# digitalclock.net
KiCad netlist of a schematic drawn in EAGLE
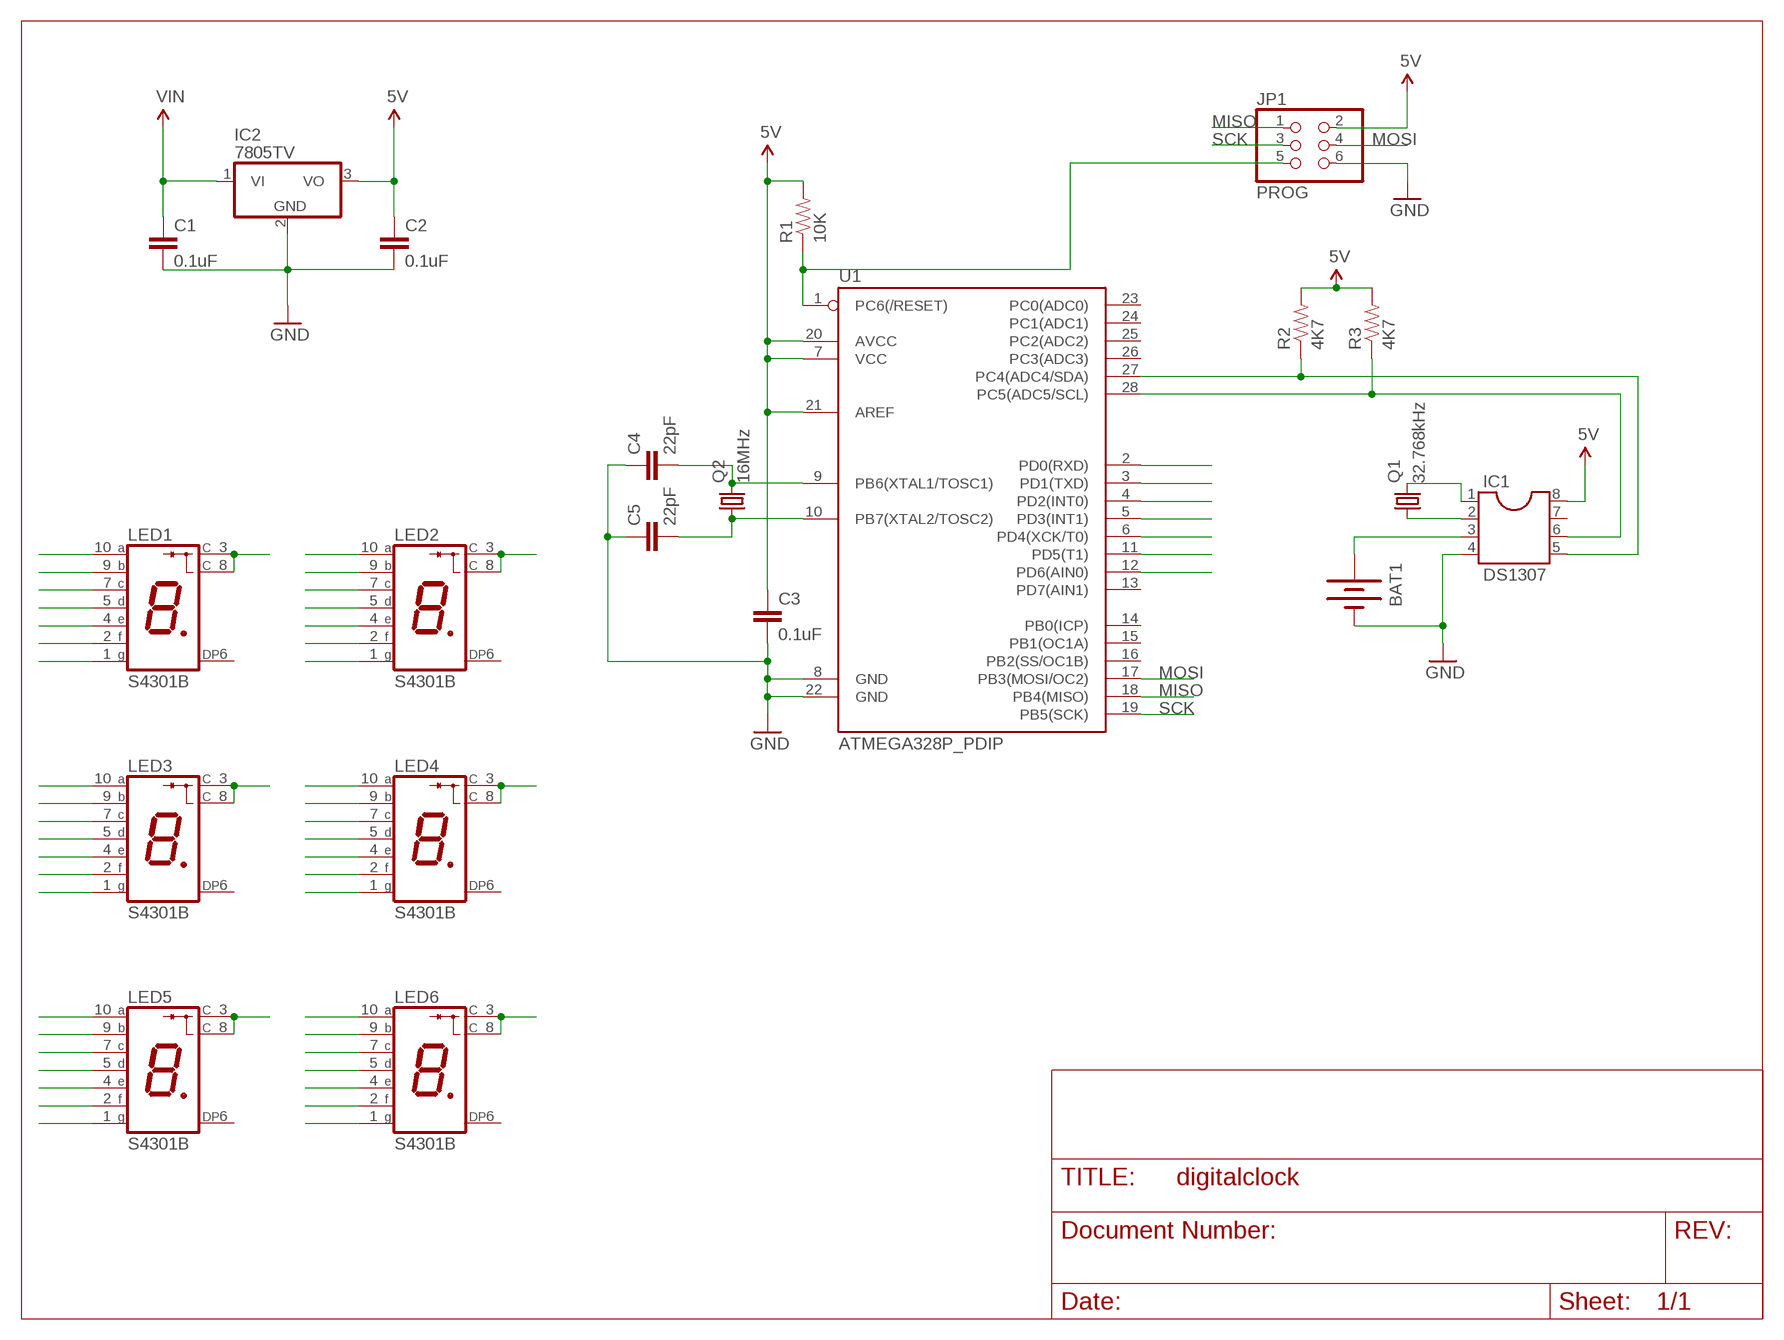
[diagram p0: schematic, sheet 1]

(export (version "E")
  (design (tool "Eeschema 10.0.6"))
  (components
    (comp (ref "BAT1")
      (value "BATTERY20PTH")
      (footprint "eagle-import:BATTCOM_20MM_PTH")
      (libsource (lib "eagle-import") (part "BATTERY20PTH"))
    )
    (comp (ref "C1")
      (value "0.1uF")
      (footprint "eagle-import:CAP-PTH-SMALL")
      (libsource (lib "eagle-import") (part "CAPPTH"))
    )
    (comp (ref "C2")
      (value "0.1uF")
      (footprint "eagle-import:CAP-PTH-SMALL")
      (libsource (lib "eagle-import") (part "CAPPTH"))
    )
    (comp (ref "C3")
      (value "0.1uF")
      (footprint "eagle-import:CAP-PTH-SMALL")
      (libsource (lib "eagle-import") (part "CAPPTH"))
    )
    (comp (ref "C4")
      (value "22pF")
      (footprint "eagle-import:CAP-PTH-SMALL")
      (libsource (lib "eagle-import") (part "CAPPTH"))
    )
    (comp (ref "C5")
      (value "22pF")
      (footprint "eagle-import:CAP-PTH-SMALL")
      (libsource (lib "eagle-import") (part "CAPPTH"))
    )
    (comp (ref "IC1")
      (value "DS1307")
      (footprint "eagle-import:SOCKET-08")
      (libsource (lib "eagle-import") (part "DIL8S"))
    )
    (comp (ref "IC2")
      (value "7805TV")
      (footprint "eagle-import:TO220V")
      (libsource (lib "eagle-import") (part "78TV05"))
    )
    (comp (ref "JP1")
      (value "PROG")
      (footprint "eagle-import:2X03")
      (libsource (lib "eagle-import") (part "PINHD-2X3"))
    )
    (comp (ref "LED1")
      (value "S4301B")
      (footprint "eagle-import:S4301B")
      (libsource (lib "eagle-import") (part "S4301B"))
    )
    (comp (ref "LED2")
      (value "S4301B")
      (footprint "eagle-import:S4301B")
      (libsource (lib "eagle-import") (part "S4301B"))
    )
    (comp (ref "LED3")
      (value "S4301B")
      (footprint "eagle-import:S4301B")
      (libsource (lib "eagle-import") (part "S4301B"))
    )
    (comp (ref "LED4")
      (value "S4301B")
      (footprint "eagle-import:S4301B")
      (libsource (lib "eagle-import") (part "S4301B"))
    )
    (comp (ref "LED5")
      (value "S4301B")
      (footprint "eagle-import:S4301B")
      (libsource (lib "eagle-import") (part "S4301B"))
    )
    (comp (ref "LED6")
      (value "S4301B")
      (footprint "eagle-import:S4301B")
      (libsource (lib "eagle-import") (part "S4301B"))
    )
    (comp (ref "Q1")
      (value "32.768kHz")
      (footprint "eagle-import:TC26V")
      (libsource (lib "eagle-import") (part "CRYSTALTC26V"))
    )
    (comp (ref "Q2")
      (value "16MHz")
      (footprint "eagle-import:HC49_S")
      (libsource (lib "eagle-import") (part "CRYSTALHC49S"))
    )
    (comp (ref "R1")
      (value "10K")
      (footprint "eagle-import:AXIAL-0.3")
      (libsource (lib "eagle-import") (part "RESISTORAXIAL-0.3"))
    )
    (comp (ref "R2")
      (value "4K7")
      (footprint "eagle-import:AXIAL-0.3")
      (libsource (lib "eagle-import") (part "RESISTORAXIAL-0.3"))
    )
    (comp (ref "R3")
      (value "4K7")
      (footprint "eagle-import:AXIAL-0.3")
      (libsource (lib "eagle-import") (part "RESISTORAXIAL-0.3"))
    )
    (comp (ref "U1")
      (value "ATMEGA328P_PDIP")
      (footprint "eagle-import:DIL28-3")
      (libsource (lib "eagle-import") (part "ATMEGA328P_PDIP"))
    )
  )
  (nets
    (net (code "1") (name "/MISO") (class "Default")
      (node (ref "JP1") (pin "1") (pinfunction "1_1") (pintype "passive"))
      (node (ref "U1") (pin "18") (pinfunction "PB4(MISO)_18") (pintype "bidirectional"))
    )
    (net (code "2") (name "/MOSI") (class "Default")
      (node (ref "JP1") (pin "4") (pinfunction "4_4") (pintype "passive"))
      (node (ref "U1") (pin "17") (pinfunction "PB3(MOSI/OC2)_17") (pintype "bidirectional"))
    )
    (net (code "3") (name "/SCK") (class "Default")
      (node (ref "JP1") (pin "3") (pinfunction "3_3") (pintype "passive"))
      (node (ref "U1") (pin "19") (pinfunction "PB5(SCK)_19") (pintype "bidirectional"))
    )
    (net (code "4") (name "5V") (class "Default")
      (node (ref "C2") (pin "1") (pinfunction "1_1") (pintype "passive"))
      (node (ref "C3") (pin "1") (pinfunction "1_1") (pintype "passive"))
      (node (ref "IC1") (pin "8") (pinfunction "8_8") (pintype "passive"))
      (node (ref "IC2") (pin "3") (pinfunction "VO_3") (pintype "passive"))
      (node (ref "JP1") (pin "2") (pinfunction "2_2") (pintype "passive"))
      (node (ref "R1") (pin "P$2") (pinfunction "2_P$2") (pintype "passive"))
      (node (ref "R2") (pin "P$2") (pinfunction "2_P$2") (pintype "passive"))
      (node (ref "R3") (pin "P$2") (pinfunction "2_P$2") (pintype "passive"))
      (node (ref "U1") (pin "20") (pinfunction "AVCC_20") (pintype "bidirectional"))
      (node (ref "U1") (pin "21") (pinfunction "AREF_21") (pintype "bidirectional"))
      (node (ref "U1") (pin "7") (pinfunction "VCC_7") (pintype "bidirectional"))
    )
    (net (code "5") (name "GND") (class "Default")
      (node (ref "BAT1") (pin "2") (pinfunction "-_2") (pintype "power_in"))
      (node (ref "C1") (pin "2") (pinfunction "2_2") (pintype "passive"))
      (node (ref "C2") (pin "2") (pinfunction "2_2") (pintype "passive"))
      (node (ref "C3") (pin "2") (pinfunction "2_2") (pintype "passive"))
      (node (ref "C4") (pin "1") (pinfunction "1_1") (pintype "passive"))
      (node (ref "C5") (pin "1") (pinfunction "1_1") (pintype "passive"))
      (node (ref "IC1") (pin "4") (pinfunction "4_4") (pintype "passive"))
      (node (ref "IC2") (pin "2") (pinfunction "GND_2") (pintype "passive"))
      (node (ref "JP1") (pin "6") (pinfunction "6_6") (pintype "passive"))
      (node (ref "U1") (pin "22") (pinfunction "GND_22") (pintype "bidirectional"))
      (node (ref "U1") (pin "8") (pinfunction "GND_8") (pintype "bidirectional"))
    )
    (net (code "6") (name "Net-(BAT1-+)") (class "Default")
      (node (ref "BAT1") (pin "1") (pinfunction "+_1") (pintype "power_in"))
      (node (ref "IC1") (pin "3") (pinfunction "3_3") (pintype "passive"))
    )
    (net (code "7") (name "Net-(IC1-Pad1)") (class "Default")
      (node (ref "IC1") (pin "1") (pinfunction "1_1") (pintype "passive"))
      (node (ref "Q1") (pin "2") (pinfunction "2_2") (pintype "passive"))
    )
    (net (code "8") (name "Net-(IC1-Pad2)") (class "Default")
      (node (ref "IC1") (pin "2") (pinfunction "2_2") (pintype "passive"))
      (node (ref "Q1") (pin "1") (pinfunction "1_1") (pintype "passive"))
    )
    (net (code "9") (name "Net-(LED1-C-Pad3)") (class "Default")
      (node (ref "LED1") (pin "3") (pinfunction "C_3") (pintype "passive"))
      (node (ref "LED1") (pin "8") (pinfunction "C_8") (pintype "passive"))
    )
    (net (code "10") (name "Net-(LED2-C-Pad3)") (class "Default")
      (node (ref "LED2") (pin "3") (pinfunction "C_3") (pintype "passive"))
      (node (ref "LED2") (pin "8") (pinfunction "C_8") (pintype "passive"))
    )
    (net (code "11") (name "Net-(LED3-C-Pad3)") (class "Default")
      (node (ref "LED3") (pin "3") (pinfunction "C_3") (pintype "passive"))
      (node (ref "LED3") (pin "8") (pinfunction "C_8") (pintype "passive"))
    )
    (net (code "12") (name "Net-(LED4-C-Pad3)") (class "Default")
      (node (ref "LED4") (pin "3") (pinfunction "C_3") (pintype "passive"))
      (node (ref "LED4") (pin "8") (pinfunction "C_8") (pintype "passive"))
    )
    (net (code "13") (name "Net-(LED5-C-Pad3)") (class "Default")
      (node (ref "LED5") (pin "3") (pinfunction "C_3") (pintype "passive"))
      (node (ref "LED5") (pin "8") (pinfunction "C_8") (pintype "passive"))
    )
    (net (code "14") (name "Net-(LED6-C-Pad3)") (class "Default")
      (node (ref "LED6") (pin "3") (pinfunction "C_3") (pintype "passive"))
      (node (ref "LED6") (pin "8") (pinfunction "C_8") (pintype "passive"))
    )
    (net (code "15") (name "Net-(R1-1)") (class "Default")
      (node (ref "JP1") (pin "5") (pinfunction "5_5") (pintype "passive"))
      (node (ref "R1") (pin "P$1") (pinfunction "1_P$1") (pintype "passive"))
      (node (ref "U1") (pin "1") (pinfunction "PC6(/RESET)_1") (pintype "bidirectional"))
    )
    (net (code "16") (name "Net-(R2-1)") (class "Default")
      (node (ref "IC1") (pin "5") (pinfunction "5_5") (pintype "passive"))
      (node (ref "R2") (pin "P$1") (pinfunction "1_P$1") (pintype "passive"))
      (node (ref "U1") (pin "27") (pinfunction "PC4(ADC4/SDA)_27") (pintype "bidirectional"))
    )
    (net (code "17") (name "Net-(R3-1)") (class "Default")
      (node (ref "IC1") (pin "6") (pinfunction "6_6") (pintype "passive"))
      (node (ref "R3") (pin "P$1") (pinfunction "1_P$1") (pintype "passive"))
      (node (ref "U1") (pin "28") (pinfunction "PC5(ADC5/SCL)_28") (pintype "bidirectional"))
    )
    (net (code "18") (name "Net-(U1-PB6(XTAL1{slash}TOSC1))") (class "Default")
      (node (ref "C4") (pin "2") (pinfunction "2_2") (pintype "passive"))
      (node (ref "Q2") (pin "2") (pinfunction "2_2") (pintype "passive"))
      (node (ref "U1") (pin "9") (pinfunction "PB6(XTAL1/TOSC1)_9") (pintype "bidirectional"))
    )
    (net (code "19") (name "Net-(U1-PB7(XTAL2{slash}TOSC2))") (class "Default")
      (node (ref "C5") (pin "2") (pinfunction "2_2") (pintype "passive"))
      (node (ref "Q2") (pin "1") (pinfunction "1_1") (pintype "passive"))
      (node (ref "U1") (pin "10") (pinfunction "PB7(XTAL2/TOSC2)_10") (pintype "bidirectional"))
    )
    (net (code "20") (name "VIN") (class "Default")
      (node (ref "C1") (pin "1") (pinfunction "1_1") (pintype "passive"))
      (node (ref "IC2") (pin "1") (pinfunction "VI_1") (pintype "input"))
    )
    (net (code "21") (name "unconnected-(IC1-Pad7)") (class "Default")
      (node (ref "IC1") (pin "7") (pinfunction "7_7") (pintype "passive"))
    )
    (net (code "22") (name "unconnected-(LED1-A-Pad10)") (class "Default")
      (node (ref "LED1") (pin "10") (pinfunction "A_10") (pintype "passive"))
    )
    (net (code "23") (name "unconnected-(LED1-B-Pad9)") (class "Default")
      (node (ref "LED1") (pin "9") (pinfunction "B_9") (pintype "passive"))
    )
    (net (code "24") (name "unconnected-(LED1-C-Pad7)") (class "Default")
      (node (ref "LED1") (pin "7") (pinfunction "C_7") (pintype "passive"))
    )
    (net (code "25") (name "unconnected-(LED1-D-Pad5)") (class "Default")
      (node (ref "LED1") (pin "5") (pinfunction "D_5") (pintype "passive"))
    )
    (net (code "26") (name "unconnected-(LED1-DP-Pad6)") (class "Default")
      (node (ref "LED1") (pin "6") (pinfunction "DP_6") (pintype "passive"))
    )
    (net (code "27") (name "unconnected-(LED1-E-Pad4)") (class "Default")
      (node (ref "LED1") (pin "4") (pinfunction "E_4") (pintype "passive"))
    )
    (net (code "28") (name "unconnected-(LED1-F-Pad2)") (class "Default")
      (node (ref "LED1") (pin "2") (pinfunction "F_2") (pintype "passive"))
    )
    (net (code "29") (name "unconnected-(LED1-G-Pad1)") (class "Default")
      (node (ref "LED1") (pin "1") (pinfunction "G_1") (pintype "passive"))
    )
    (net (code "30") (name "unconnected-(LED2-A-Pad10)") (class "Default")
      (node (ref "LED2") (pin "10") (pinfunction "A_10") (pintype "passive"))
    )
    (net (code "31") (name "unconnected-(LED2-B-Pad9)") (class "Default")
      (node (ref "LED2") (pin "9") (pinfunction "B_9") (pintype "passive"))
    )
    (net (code "32") (name "unconnected-(LED2-C-Pad7)") (class "Default")
      (node (ref "LED2") (pin "7") (pinfunction "C_7") (pintype "passive"))
    )
    (net (code "33") (name "unconnected-(LED2-D-Pad5)") (class "Default")
      (node (ref "LED2") (pin "5") (pinfunction "D_5") (pintype "passive"))
    )
    (net (code "34") (name "unconnected-(LED2-DP-Pad6)") (class "Default")
      (node (ref "LED2") (pin "6") (pinfunction "DP_6") (pintype "passive"))
    )
    (net (code "35") (name "unconnected-(LED2-E-Pad4)") (class "Default")
      (node (ref "LED2") (pin "4") (pinfunction "E_4") (pintype "passive"))
    )
    (net (code "36") (name "unconnected-(LED2-F-Pad2)") (class "Default")
      (node (ref "LED2") (pin "2") (pinfunction "F_2") (pintype "passive"))
    )
    (net (code "37") (name "unconnected-(LED2-G-Pad1)") (class "Default")
      (node (ref "LED2") (pin "1") (pinfunction "G_1") (pintype "passive"))
    )
    (net (code "38") (name "unconnected-(LED3-A-Pad10)") (class "Default")
      (node (ref "LED3") (pin "10") (pinfunction "A_10") (pintype "passive"))
    )
    (net (code "39") (name "unconnected-(LED3-B-Pad9)") (class "Default")
      (node (ref "LED3") (pin "9") (pinfunction "B_9") (pintype "passive"))
    )
    (net (code "40") (name "unconnected-(LED3-C-Pad7)") (class "Default")
      (node (ref "LED3") (pin "7") (pinfunction "C_7") (pintype "passive"))
    )
    (net (code "41") (name "unconnected-(LED3-D-Pad5)") (class "Default")
      (node (ref "LED3") (pin "5") (pinfunction "D_5") (pintype "passive"))
    )
    (net (code "42") (name "unconnected-(LED3-DP-Pad6)") (class "Default")
      (node (ref "LED3") (pin "6") (pinfunction "DP_6") (pintype "passive"))
    )
    (net (code "43") (name "unconnected-(LED3-E-Pad4)") (class "Default")
      (node (ref "LED3") (pin "4") (pinfunction "E_4") (pintype "passive"))
    )
    (net (code "44") (name "unconnected-(LED3-F-Pad2)") (class "Default")
      (node (ref "LED3") (pin "2") (pinfunction "F_2") (pintype "passive"))
    )
    (net (code "45") (name "unconnected-(LED3-G-Pad1)") (class "Default")
      (node (ref "LED3") (pin "1") (pinfunction "G_1") (pintype "passive"))
    )
    (net (code "46") (name "unconnected-(LED4-A-Pad10)") (class "Default")
      (node (ref "LED4") (pin "10") (pinfunction "A_10") (pintype "passive"))
    )
    (net (code "47") (name "unconnected-(LED4-B-Pad9)") (class "Default")
      (node (ref "LED4") (pin "9") (pinfunction "B_9") (pintype "passive"))
    )
    (net (code "48") (name "unconnected-(LED4-C-Pad7)") (class "Default")
      (node (ref "LED4") (pin "7") (pinfunction "C_7") (pintype "passive"))
    )
    (net (code "49") (name "unconnected-(LED4-D-Pad5)") (class "Default")
      (node (ref "LED4") (pin "5") (pinfunction "D_5") (pintype "passive"))
    )
    (net (code "50") (name "unconnected-(LED4-DP-Pad6)") (class "Default")
      (node (ref "LED4") (pin "6") (pinfunction "DP_6") (pintype "passive"))
    )
    (net (code "51") (name "unconnected-(LED4-E-Pad4)") (class "Default")
      (node (ref "LED4") (pin "4") (pinfunction "E_4") (pintype "passive"))
    )
    (net (code "52") (name "unconnected-(LED4-F-Pad2)") (class "Default")
      (node (ref "LED4") (pin "2") (pinfunction "F_2") (pintype "passive"))
    )
    (net (code "53") (name "unconnected-(LED4-G-Pad1)") (class "Default")
      (node (ref "LED4") (pin "1") (pinfunction "G_1") (pintype "passive"))
    )
    (net (code "54") (name "unconnected-(LED5-A-Pad10)") (class "Default")
      (node (ref "LED5") (pin "10") (pinfunction "A_10") (pintype "passive"))
    )
    (net (code "55") (name "unconnected-(LED5-B-Pad9)") (class "Default")
      (node (ref "LED5") (pin "9") (pinfunction "B_9") (pintype "passive"))
    )
    (net (code "56") (name "unconnected-(LED5-C-Pad7)") (class "Default")
      (node (ref "LED5") (pin "7") (pinfunction "C_7") (pintype "passive"))
    )
    (net (code "57") (name "unconnected-(LED5-D-Pad5)") (class "Default")
      (node (ref "LED5") (pin "5") (pinfunction "D_5") (pintype "passive"))
    )
    (net (code "58") (name "unconnected-(LED5-DP-Pad6)") (class "Default")
      (node (ref "LED5") (pin "6") (pinfunction "DP_6") (pintype "passive"))
    )
    (net (code "59") (name "unconnected-(LED5-E-Pad4)") (class "Default")
      (node (ref "LED5") (pin "4") (pinfunction "E_4") (pintype "passive"))
    )
    (net (code "60") (name "unconnected-(LED5-F-Pad2)") (class "Default")
      (node (ref "LED5") (pin "2") (pinfunction "F_2") (pintype "passive"))
    )
    (net (code "61") (name "unconnected-(LED5-G-Pad1)") (class "Default")
      (node (ref "LED5") (pin "1") (pinfunction "G_1") (pintype "passive"))
    )
    (net (code "62") (name "unconnected-(LED6-A-Pad10)") (class "Default")
      (node (ref "LED6") (pin "10") (pinfunction "A_10") (pintype "passive"))
    )
    (net (code "63") (name "unconnected-(LED6-B-Pad9)") (class "Default")
      (node (ref "LED6") (pin "9") (pinfunction "B_9") (pintype "passive"))
    )
    (net (code "64") (name "unconnected-(LED6-C-Pad7)") (class "Default")
      (node (ref "LED6") (pin "7") (pinfunction "C_7") (pintype "passive"))
    )
    (net (code "65") (name "unconnected-(LED6-D-Pad5)") (class "Default")
      (node (ref "LED6") (pin "5") (pinfunction "D_5") (pintype "passive"))
    )
    (net (code "66") (name "unconnected-(LED6-DP-Pad6)") (class "Default")
      (node (ref "LED6") (pin "6") (pinfunction "DP_6") (pintype "passive"))
    )
    (net (code "67") (name "unconnected-(LED6-E-Pad4)") (class "Default")
      (node (ref "LED6") (pin "4") (pinfunction "E_4") (pintype "passive"))
    )
    (net (code "68") (name "unconnected-(LED6-F-Pad2)") (class "Default")
      (node (ref "LED6") (pin "2") (pinfunction "F_2") (pintype "passive"))
    )
    (net (code "69") (name "unconnected-(LED6-G-Pad1)") (class "Default")
      (node (ref "LED6") (pin "1") (pinfunction "G_1") (pintype "passive"))
    )
    (net (code "70") (name "unconnected-(U1-PB0(ICP)-Pad14)") (class "Default")
      (node (ref "U1") (pin "14") (pinfunction "PB0(ICP)_14") (pintype "bidirectional"))
    )
    (net (code "71") (name "unconnected-(U1-PB1(OC1A)-Pad15)") (class "Default")
      (node (ref "U1") (pin "15") (pinfunction "PB1(OC1A)_15") (pintype "bidirectional"))
    )
    (net (code "72") (name "unconnected-(U1-PB2(SS{slash}OC1B)-Pad16)") (class "Default")
      (node (ref "U1") (pin "16") (pinfunction "PB2(SS/OC1B)_16") (pintype "bidirectional"))
    )
    (net (code "73") (name "unconnected-(U1-PC0(ADC0)-Pad23)") (class "Default")
      (node (ref "U1") (pin "23") (pinfunction "PC0(ADC0)_23") (pintype "bidirectional"))
    )
    (net (code "74") (name "unconnected-(U1-PC1(ADC1)-Pad24)") (class "Default")
      (node (ref "U1") (pin "24") (pinfunction "PC1(ADC1)_24") (pintype "bidirectional"))
    )
    (net (code "75") (name "unconnected-(U1-PC2(ADC2)-Pad25)") (class "Default")
      (node (ref "U1") (pin "25") (pinfunction "PC2(ADC2)_25") (pintype "bidirectional"))
    )
    (net (code "76") (name "unconnected-(U1-PC3(ADC3)-Pad26)") (class "Default")
      (node (ref "U1") (pin "26") (pinfunction "PC3(ADC3)_26") (pintype "bidirectional"))
    )
    (net (code "77") (name "unconnected-(U1-PD0(RXD)-Pad2)") (class "Default")
      (node (ref "U1") (pin "2") (pinfunction "PD0(RXD)_2") (pintype "bidirectional"))
    )
    (net (code "78") (name "unconnected-(U1-PD1(TXD)-Pad3)") (class "Default")
      (node (ref "U1") (pin "3") (pinfunction "PD1(TXD)_3") (pintype "bidirectional"))
    )
    (net (code "79") (name "unconnected-(U1-PD2(INT0)-Pad4)") (class "Default")
      (node (ref "U1") (pin "4") (pinfunction "PD2(INT0)_4") (pintype "bidirectional"))
    )
    (net (code "80") (name "unconnected-(U1-PD3(INT1)-Pad5)") (class "Default")
      (node (ref "U1") (pin "5") (pinfunction "PD3(INT1)_5") (pintype "bidirectional"))
    )
    (net (code "81") (name "unconnected-(U1-PD4(XCK{slash}T0)-Pad6)") (class "Default")
      (node (ref "U1") (pin "6") (pinfunction "PD4(XCK/T0)_6") (pintype "bidirectional"))
    )
    (net (code "82") (name "unconnected-(U1-PD5(T1)-Pad11)") (class "Default")
      (node (ref "U1") (pin "11") (pinfunction "PD5(T1)_11") (pintype "bidirectional"))
    )
    (net (code "83") (name "unconnected-(U1-PD6(AIN0)-Pad12)") (class "Default")
      (node (ref "U1") (pin "12") (pinfunction "PD6(AIN0)_12") (pintype "bidirectional"))
    )
    (net (code "84") (name "unconnected-(U1-PD7(AIN1)-Pad13)") (class "Default")
      (node (ref "U1") (pin "13") (pinfunction "PD7(AIN1)_13") (pintype "bidirectional"))
    )
  )
)
